# esp8266.net
KiCad netlist of a schematic drawn in EasyEDA Pro
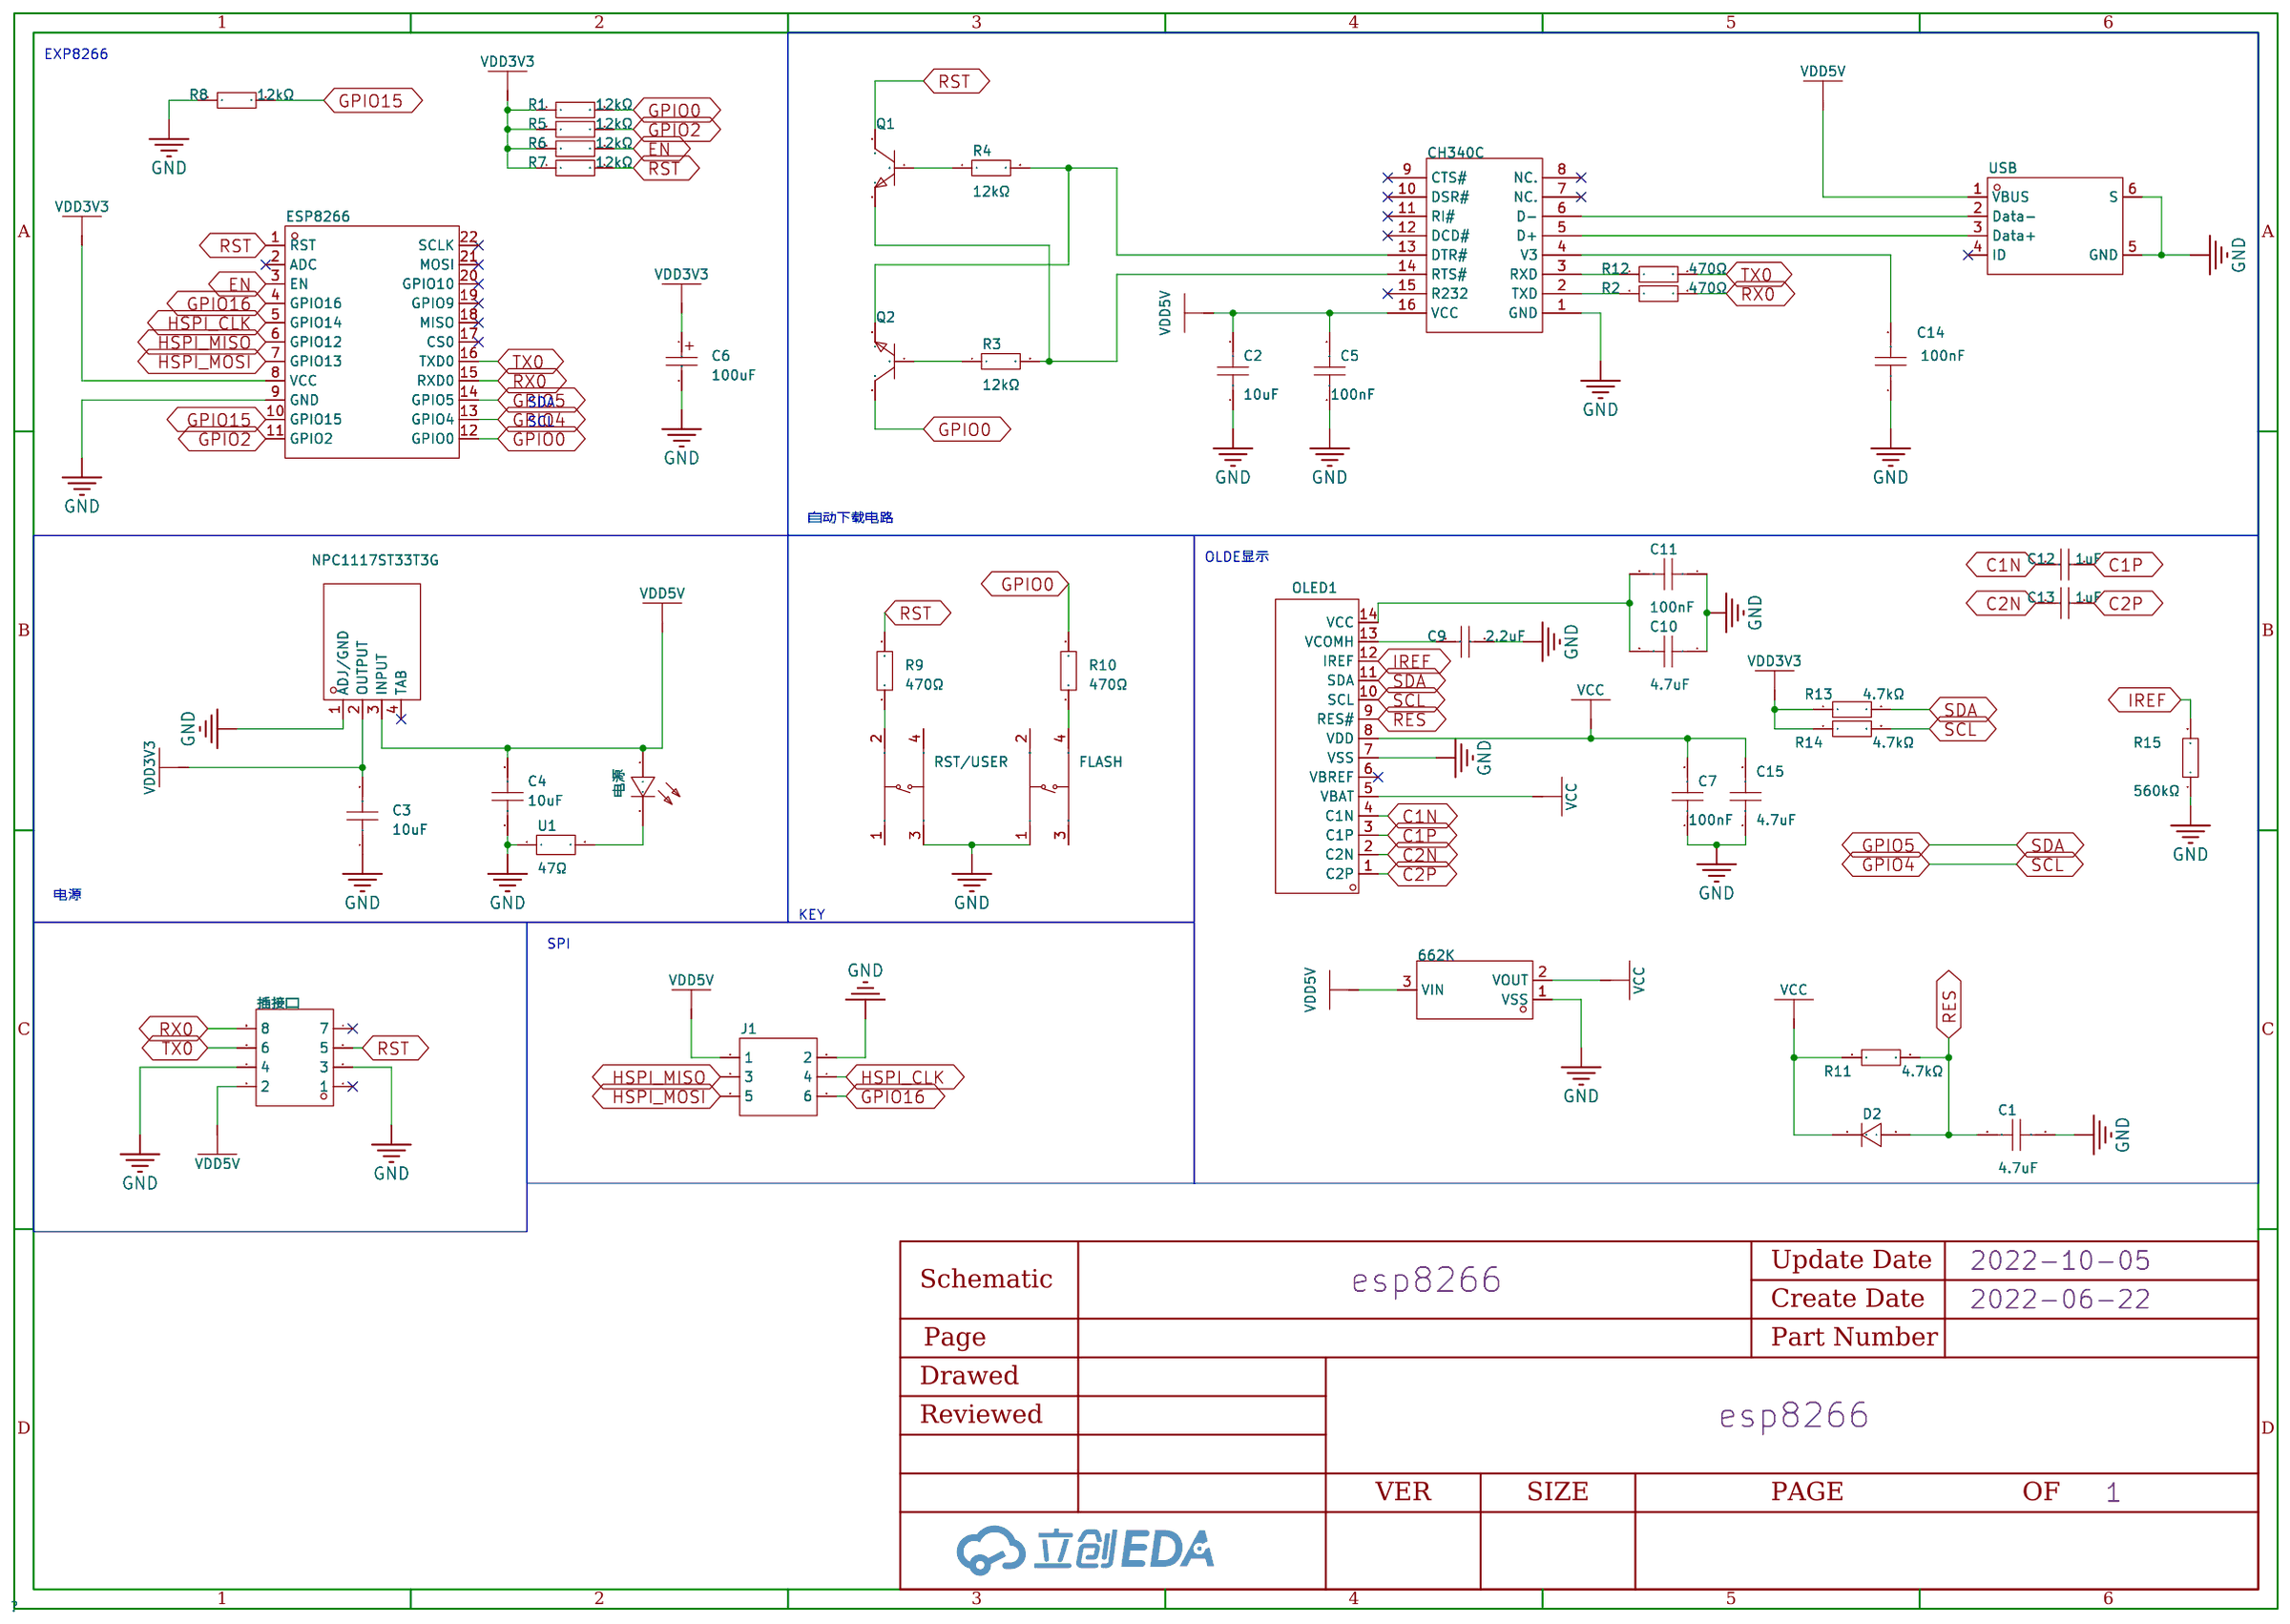
[diagram p0: schematic sheet]

(export (version "E")
  (design (tool "Eeschema 10.0.6"))
  (components
    (comp (ref "662K")
      (value "~")
      (footprint "easyedapro:SOT-23-3_L2.9-W1.3-P1.90-LS2.4-BR")
      (description "输出类型:-;")
      (fields (field (name "Manufacturer Part") "662K.") (field (name "Manufacturer") "FM富满"))
      (libsource (lib "easyedapro") (part "662K."))
    )
    (comp (ref "C1")
      (value "4.7uF")
      (footprint "easyedapro:C0805")
      (description "容值:4.7uF;精度:±10%;额定电压:25V;温度系数:X5R;")
      (fields
        (field (name "Manufacturer Part") "TMK212ABJ475KG-T")
        (field (name "Manufacturer") "TAIYO YUDEN(太诱)")
      )
      (libsource (lib "easyedapro") (part "TMK212ABJ475KG-T"))
    )
    (comp (ref "C2")
      (value "10uF")
      (footprint "easyedapro:C0805")
      (description "容值:10uF;精度:±10%;额定电压:-;温度系数:-;")
      (fields
        (field (name "Manufacturer Part") "GRT21BC71E106KE13L")
        (field (name "Manufacturer") "muRata(村田)")
      )
      (libsource (lib "easyedapro") (part "GRT21BC71E106KE13L"))
    )
    (comp (ref "C3")
      (value "10uF")
      (footprint "easyedapro:C0805")
      (description "容值:10uF;精度:±10%;额定电压:-;温度系数:-;")
      (fields
        (field (name "Manufacturer Part") "GRT21BC71E106KE13L")
        (field (name "Manufacturer") "muRata(村田)")
      )
      (libsource (lib "easyedapro") (part "GRT21BC71E106KE13L"))
    )
    (comp (ref "C4")
      (value "10uF")
      (footprint "easyedapro:C0805")
      (description "容值:10uF;精度:±10%;额定电压:-;温度系数:-;")
      (fields
        (field (name "Manufacturer Part") "GRT21BC71E106KE13L")
        (field (name "Manufacturer") "muRata(村田)")
      )
      (libsource (lib "easyedapro") (part "GRT21BC71E106KE13L"))
    )
    (comp (ref "C5")
      (value "100nF")
      (footprint "easyedapro:C0805")
      (description "容值:100nF;精度:±10%;额定电压:100V;温度系数:X7R;")
      (fields (field (name "Manufacturer Part") "C0805X104K101T") (field (name "Manufacturer") "IHHEC(禾伸堂)"))
      (libsource (lib "easyedapro") (part "C0805X104K101T_C485772"))
    )
    (comp (ref "C6")
      (value "100uF")
      (footprint "easyedapro:CAP-SMD_L3.5-W2.8-R-RD")
      (description "容值:100uF;精度:±20%;额定电压:6.3V;等效串联电阻:1.7Ω@100kHz;工作温度:-55~+125;")
      (fields (field (name "Manufacturer Part") "TAJB107M006RNJ") (field (name "Manufacturer") "AVX"))
      (libsource (lib "easyedapro") (part "TAJB107M006RNJ"))
    )
    (comp (ref "C7")
      (value "100nF")
      (footprint "easyedapro:C0805")
      (description "容值:100nF;精度:±10%;额定电压:100V;温度系数:X7R;")
      (fields (field (name "Manufacturer Part") "C0805X104K101T") (field (name "Manufacturer") "IHHEC(禾伸堂)"))
      (libsource (lib "easyedapro") (part "C0805X104K101T_C485772"))
    )
    (comp (ref "C9")
      (value "2.2uF")
      (footprint "easyedapro:C0805")
      (description "容值:2.2uF;精度:-20%~+80%;额定电压:25V;温度系数:Y5V;")
      (fields
        (field (name "Manufacturer Part") "CL21F225ZAFNNNE")
        (field (name "Manufacturer") "SAMSUNG(三星)")
      )
      (libsource (lib "easyedapro") (part "CL21F225ZAFNNNE"))
    )
    (comp (ref "C10")
      (value "4.7uF")
      (footprint "easyedapro:C0805")
      (description "容值:4.7uF;精度:±10%;额定电压:-;温度系数:-;")
      (fields
        (field (name "Manufacturer Part") "GRM219B31A475KE33D")
        (field (name "Manufacturer") "muRata(村田)")
      )
      (libsource (lib "easyedapro") (part "GRM219B31A475KE33D"))
    )
    (comp (ref "C11")
      (value "100nF")
      (footprint "easyedapro:C0805")
      (description "容值:100nF;精度:±10%;额定电压:100V;温度系数:X7R;")
      (fields (field (name "Manufacturer Part") "C0805X104K101T") (field (name "Manufacturer") "IHHEC(禾伸堂)"))
      (libsource (lib "easyedapro") (part "C0805X104K101T_C485772"))
    )
    (comp (ref "C12")
      (value "1uF")
      (footprint "easyedapro:C0805")
      (description "容值:1uF;精度:-20%~+80%;额定电压:16V;温度系数:Y5V;")
      (fields
        (field (name "Manufacturer Part") "CL21F105ZOFNNNE")
        (field (name "Manufacturer") "SAMSUNG(三星)")
      )
      (libsource (lib "easyedapro") (part "CL21F105ZOFNNNE"))
    )
    (comp (ref "C13")
      (value "1uF")
      (footprint "easyedapro:C0805")
      (description "容值:1uF;精度:-20%~+80%;额定电压:16V;温度系数:Y5V;")
      (fields
        (field (name "Manufacturer Part") "CL21F105ZOFNNNE")
        (field (name "Manufacturer") "SAMSUNG(三星)")
      )
      (libsource (lib "easyedapro") (part "CL21F105ZOFNNNE"))
    )
    (comp (ref "C14")
      (value "100nF")
      (footprint "easyedapro:C0805")
      (description "容值:100nF;精度:±10%;额定电压:100V;温度系数:X7R;")
      (fields (field (name "Manufacturer Part") "C0805X104K101T") (field (name "Manufacturer") "IHHEC(禾伸堂)"))
      (libsource (lib "easyedapro") (part "C0805X104K101T_C485772"))
    )
    (comp (ref "C15")
      (value "4.7uF")
      (footprint "easyedapro:C0805")
      (description "容值:4.7uF;精度:±10%;额定电压:25V;温度系数:X5R;")
      (fields
        (field (name "Manufacturer Part") "TMK212ABJ475KG-T")
        (field (name "Manufacturer") "TAIYO YUDEN(太诱)")
      )
      (libsource (lib "easyedapro") (part "TMK212ABJ475KG-T"))
    )
    (comp (ref "CH340C")
      (value "~")
      (footprint "easyedapro:SOP-16_L10.0-W3.9-P1.27-LS6.0-BL")
      (description "类型:Transceiver;协议类别:USB 2.0;驱动器/接收器数:-;数据速率:2Mbps;")
      (fields (field (name "Manufacturer Part") "CH340C") (field (name "Manufacturer") "WCH(南京沁恒)"))
      (libsource (lib "easyedapro") (part "CH340C"))
    )
    (comp (ref "D2")
      (value "~")
      (footprint "easyedapro:SOD-323_L1.8-W1.3-LS2.5-RD")
      (fields (field (name "Manufacturer Part") "1N4148WS") (field (name "Manufacturer") "CJ（江苏长电/长晶）"))
      (libsource (lib "easyedapro") (part "1N4148WS T4"))
    )
    (comp (ref "ESP8266")
      (value "~")
      (footprint "easyedapro:WIFIM-SMD_ESP-12F-ESP8266MOD")
      (description "屏蔽罩上的丝印是：ESP8266MOD，ESP8266EX串口WIFI")
      (fields
        (field (name "Manufacturer Part") "ESP-12F(ESP8266MOD)")
        (field (name "Manufacturer") "Ai-Thinker(安信可)")
      )
      (libsource (lib "easyedapro") (part "ESP-12F(ESP8266MOD)"))
    )
    (comp (ref "FLASH")
      (value "~")
      (footprint "easyedapro:SW-TH_4P-L6.0-W6.0-P4.50-LS6.5")
      (description "触点电流:50mA;额定电压(DC):12V;电路结构:单刀单掷;安装方式:直插;按钮形状:圆形按钮;带灯:-;开关长度:6mm;开关宽度:6mm;开关高度:5mm;")
      (fields (field (name "Manufacturer Part") "TS665CJ") (field (name "Manufacturer") "SHOU HAN(首韩)"))
      (libsource (lib "easyedapro") (part "TS665CJ"))
    )
    (comp (ref "J1")
      (value "~")
      (footprint "easyedapro:HDR-TH_6P-P2.54-V-M-R2-C3-S2.54-1")
      (fields (field (name "Manufacturer Part") "2.54-2*3P针") (field (name "Manufacturer") "BOOMELE(博穆精密)"))
      (libsource (lib "easyedapro") (part "Header-Male-2.54_2x3"))
    )
    (comp (ref "NPC1117ST33T3G")
      (value "~")
      (footprint "easyedapro:SOT-223-3_L6.5-W3.4-P2.30-LS7.0-BR")
      (description "输出类型:固定;输出极性:正;输出通道数:1;最大输入电压:20V;输出电压:3.3V;压差:1.2V@(800mA);输出电流:1A;电源纹波抑制比(PRSS):64dB@(120Hz);")
      (fields (field (name "Manufacturer Part") "NCP1117ST33T3G") (field (name "Manufacturer") "onsemi(安森美)"))
      (libsource (lib "easyedapro") (part "NCP1117ST33T3G"))
    )
    (comp (ref "OLED1")
      (value "~")
      (footprint "easyedapro:OLED_QG-2832TLBFG02")
      (fields
        (field (name "Manufacturer Part") "QG-2832TLBFG02")
        (field (name "Manufacturer") "全智景Allvision")
      )
      (libsource (lib "easyedapro") (part "QG-2832TLBFG02"))
    )
    (comp (ref "Q1")
      (value "~")
      (footprint "easyedapro:SOT-23-3_L2.9-W1.3-P1.90-LS2.4-BR")
      (fields (field (name "Manufacturer Part") "MMBT3904") (field (name "Manufacturer") "CJ（江苏长电/长晶）"))
      (libsource (lib "easyedapro") (part "MMBT3904"))
    )
    (comp (ref "Q2")
      (value "~")
      (footprint "easyedapro:SOT-23-3_L2.9-W1.3-P1.90-LS2.4-BR")
      (fields (field (name "Manufacturer Part") "MMBT3904") (field (name "Manufacturer") "CJ（江苏长电/长晶）"))
      (libsource (lib "easyedapro") (part "MMBT3904"))
    )
    (comp (ref "R1")
      (value "12kΩ")
      (footprint "easyedapro:R0805")
      (description "电阻类型:厚膜电阻;阻值:12kΩ;精度:±1%;功率:125mW;温度系数:±100ppm/;最大工作电压:150V;工作温度范围:-55~+155;")
      (fields
        (field (name "Manufacturer Part") "0805W8F1202T5E")
        (field (name "Manufacturer") "UNI-ROYAL(厚声)")
      )
      (libsource (lib "easyedapro") (part "0805W8F1202T5E"))
    )
    (comp (ref "R2")
      (value "470Ω")
      (footprint "easyedapro:R0805")
      (description "阻值:470Ω;精度:±1%;功率:125mW;温度系数:±100ppm/;最大工作电压:100V;工作温度范围:-55~+155;")
      (fields (field (name "Manufacturer Part") "RS-05K4700FT") (field (name "Manufacturer") "FH(风华)"))
      (libsource (lib "easyedapro") (part "RS-05K4700FT"))
    )
    (comp (ref "R3")
      (value "12kΩ")
      (footprint "easyedapro:R0805")
      (description "电阻类型:厚膜电阻;阻值:12kΩ;精度:±1%;功率:125mW;温度系数:±100ppm/;最大工作电压:150V;工作温度范围:-55~+155;")
      (fields
        (field (name "Manufacturer Part") "0805W8F1202T5E")
        (field (name "Manufacturer") "UNI-ROYAL(厚声)")
      )
      (libsource (lib "easyedapro") (part "0805W8F1202T5E"))
    )
    (comp (ref "R4")
      (value "12kΩ")
      (footprint "easyedapro:R0805")
      (description "电阻类型:厚膜电阻;阻值:12kΩ;精度:±1%;功率:125mW;温度系数:±100ppm/;最大工作电压:150V;工作温度范围:-55~+155;")
      (fields
        (field (name "Manufacturer Part") "0805W8F1202T5E")
        (field (name "Manufacturer") "UNI-ROYAL(厚声)")
      )
      (libsource (lib "easyedapro") (part "0805W8F1202T5E"))
    )
    (comp (ref "R5")
      (value "12kΩ")
      (footprint "easyedapro:R0805")
      (description "电阻类型:厚膜电阻;阻值:12kΩ;精度:±1%;功率:125mW;温度系数:±100ppm/;最大工作电压:150V;工作温度范围:-55~+155;")
      (fields
        (field (name "Manufacturer Part") "0805W8F1202T5E")
        (field (name "Manufacturer") "UNI-ROYAL(厚声)")
      )
      (libsource (lib "easyedapro") (part "0805W8F1202T5E"))
    )
    (comp (ref "R6")
      (value "12kΩ")
      (footprint "easyedapro:R0805")
      (description "电阻类型:厚膜电阻;阻值:12kΩ;精度:±1%;功率:125mW;温度系数:±100ppm/;最大工作电压:150V;工作温度范围:-55~+155;")
      (fields
        (field (name "Manufacturer Part") "0805W8F1202T5E")
        (field (name "Manufacturer") "UNI-ROYAL(厚声)")
      )
      (libsource (lib "easyedapro") (part "0805W8F1202T5E"))
    )
    (comp (ref "R7")
      (value "12kΩ")
      (footprint "easyedapro:R0805")
      (description "电阻类型:厚膜电阻;阻值:12kΩ;精度:±1%;功率:125mW;温度系数:±100ppm/;最大工作电压:150V;工作温度范围:-55~+155;")
      (fields
        (field (name "Manufacturer Part") "0805W8F1202T5E")
        (field (name "Manufacturer") "UNI-ROYAL(厚声)")
      )
      (libsource (lib "easyedapro") (part "0805W8F1202T5E"))
    )
    (comp (ref "R8")
      (value "12kΩ")
      (footprint "easyedapro:R0805")
      (description "电阻类型:厚膜电阻;阻值:12kΩ;精度:±1%;功率:125mW;温度系数:±100ppm/;最大工作电压:150V;工作温度范围:-55~+155;")
      (fields
        (field (name "Manufacturer Part") "0805W8F1202T5E")
        (field (name "Manufacturer") "UNI-ROYAL(厚声)")
      )
      (libsource (lib "easyedapro") (part "0805W8F1202T5E"))
    )
    (comp (ref "R9")
      (value "470Ω")
      (footprint "easyedapro:R0805")
      (description "阻值:470Ω;精度:±1%;功率:125mW;温度系数:±100ppm/;最大工作电压:100V;工作温度范围:-55~+155;")
      (fields (field (name "Manufacturer Part") "RS-05K4700FT") (field (name "Manufacturer") "FH(风华)"))
      (libsource (lib "easyedapro") (part "RS-05K4700FT"))
    )
    (comp (ref "R10")
      (value "470Ω")
      (footprint "easyedapro:R0805")
      (description "阻值:470Ω;精度:±1%;功率:125mW;温度系数:±100ppm/;最大工作电压:100V;工作温度范围:-55~+155;")
      (fields (field (name "Manufacturer Part") "RS-05K4700FT") (field (name "Manufacturer") "FH(风华)"))
      (libsource (lib "easyedapro") (part "RS-05K4700FT"))
    )
    (comp (ref "R11")
      (value "4.7kΩ")
      (footprint "easyedapro:R0805")
      (description "阻值:4.7kΩ;精度:±1%;功率:0.125W;")
      (fields (field (name "Manufacturer Part") "RMC08054.7K1%N") (field (name "Manufacturer") "Tyohm(幸亚电阻)"))
      (libsource (lib "easyedapro") (part "RMC08054.7K1%N"))
    )
    (comp (ref "R12")
      (value "470Ω")
      (footprint "easyedapro:R0805")
      (description "阻值:470Ω;精度:±1%;功率:125mW;温度系数:±100ppm/;最大工作电压:100V;工作温度范围:-55~+155;")
      (fields (field (name "Manufacturer Part") "RS-05K4700FT") (field (name "Manufacturer") "FH(风华)"))
      (libsource (lib "easyedapro") (part "RS-05K4700FT"))
    )
    (comp (ref "R13")
      (value "4.7kΩ")
      (footprint "easyedapro:R0805")
      (description "阻值:4.7kΩ;精度:±1%;功率:0.125W;")
      (fields (field (name "Manufacturer Part") "RMC08054.7K1%N") (field (name "Manufacturer") "Tyohm(幸亚电阻)"))
      (libsource (lib "easyedapro") (part "RMC08054.7K1%N"))
    )
    (comp (ref "R14")
      (value "4.7kΩ")
      (footprint "easyedapro:R0805")
      (description "阻值:4.7kΩ;精度:±1%;功率:0.125W;")
      (fields (field (name "Manufacturer Part") "RMC08054.7K1%N") (field (name "Manufacturer") "Tyohm(幸亚电阻)"))
      (libsource (lib "easyedapro") (part "RMC08054.7K1%N"))
    )
    (comp (ref "R15")
      (value "560kΩ")
      (footprint "easyedapro:R0805")
      (description "电阻类型:厚膜电阻;阻值:560kΩ;精度:±1%;功率:1/8W;温度系数:±100ppm/;最大工作电压:150V;工作温度范围:-55~+155;")
      (fields
        (field (name "Manufacturer Part") "0805W8F5603T5E")
        (field (name "Manufacturer") "UNI-ROYAL(厚声)")
      )
      (libsource (lib "easyedapro") (part "0805W8F5603T5E"))
    )
    (comp (ref "RST/USER")
      (value "~")
      (footprint "easyedapro:SW-TH_4P-L6.0-W6.0-P4.50-LS6.5")
      (description "触点电流:50mA;额定电压(DC):12V;电路结构:单刀单掷;安装方式:直插;按钮形状:圆形按钮;带灯:-;开关长度:6mm;开关宽度:6mm;开关高度:5mm;")
      (fields (field (name "Manufacturer Part") "TS665CJ") (field (name "Manufacturer") "SHOU HAN(首韩)"))
      (libsource (lib "easyedapro") (part "TS665CJ"))
    )
    (comp (ref "U1")
      (value "47Ω")
      (footprint "easyedapro:RES-TH_BD2.3-L3.7-P7.70-D0.4")
      (description "电阻类型:金属膜电阻;阻值:47Ω;精度:±1%;功率:125mW;温度系数:±350ppm/;最大工作电压:200V;工作温度范围:-55~+155;")
      (fields (field (name "Manufacturer Part") "MF1/8W-47Ω±1%-OT52") (field (name "Manufacturer") "VO(翔胜)"))
      (libsource (lib "easyedapro") (part "MF1/8W-47Ω±1%-OT52"))
    )
    (comp (ref "USB")
      (value "~")
      (footprint "easyedapro:MICRO-USB-SMD_10118194-0001LF")
      (description "连接器类型:Micro-B;标准:USB 2.0;公母:母座;触点数量:5;端口数量:1;")
      (fields (field (name "Manufacturer Part") "10118194-0001LF") (field (name "Manufacturer") "Amphenol"))
      (libsource (lib "easyedapro") (part "10118194-0001LF"))
    )
    (comp (ref "插接口")
      (value "~")
      (footprint "easyedapro:HDR-TH_8P-P2.54-H-R2-C4-S2.54-W10.0_A2541WR")
      (fields (field (name "Manufacturer Part") "A2541WR-2x4P") (field (name "Manufacturer") "CJT(长江连接器)"))
      (libsource (lib "easyedapro") (part "A2541WR-2X4P"))
    )
    (comp (ref "电源")
      (value "~")
      (footprint "easyedapro:LED-TH_BD3.0-P2.54-FD")
      (fields
        (field (name "Manufacturer Part") "204-10SURD/S530-A3-L")
        (field (name "Manufacturer") "EVERLIGHT(台湾亿光)")
      )
      (libsource (lib "easyedapro") (part "204-10SURD/S530-A3-L"))
    )
  )
  (nets
    (net (code "1") (name "C1N") (class "Default")
      (node (ref "C12") (pin "2") (pinfunction "2_2") (pintype "input"))
      (node (ref "OLED1") (pin "4") (pinfunction "C1N_4") (pintype "input"))
    )
    (net (code "2") (name "C1P") (class "Default")
      (node (ref "C12") (pin "1") (pinfunction "1_1") (pintype "input"))
      (node (ref "OLED1") (pin "3") (pinfunction "C1P_3") (pintype "input"))
    )
    (net (code "3") (name "C2N") (class "Default")
      (node (ref "C13") (pin "1") (pinfunction "1_1") (pintype "input"))
      (node (ref "OLED1") (pin "2") (pinfunction "C2N_2") (pintype "input"))
    )
    (net (code "4") (name "C2P") (class "Default")
      (node (ref "C13") (pin "2") (pinfunction "2_2") (pintype "input"))
      (node (ref "OLED1") (pin "1") (pinfunction "C2P_1") (pintype "input"))
    )
    (net (code "5") (name "EN") (class "Default")
      (node (ref "ESP8266") (pin "3") (pinfunction "EN_3") (pintype "input"))
      (node (ref "R6") (pin "2") (pinfunction "2_2") (pintype "input"))
    )
    (net (code "6") (name "GND") (class "Default")
      (node (ref "662K") (pin "1") (pinfunction "VSS_1") (pintype "input"))
      (node (ref "C1") (pin "1") (pinfunction "1_1") (pintype "input"))
      (node (ref "C10") (pin "1") (pinfunction "1_1") (pintype "input"))
      (node (ref "C11") (pin "1") (pinfunction "1_1") (pintype "input"))
      (node (ref "C14") (pin "1") (pinfunction "1_1") (pintype "input"))
      (node (ref "C15") (pin "1") (pinfunction "1_1") (pintype "input"))
      (node (ref "C2") (pin "1") (pinfunction "1_1") (pintype "input"))
      (node (ref "C3") (pin "1") (pinfunction "1_1") (pintype "input"))
      (node (ref "C4") (pin "1") (pinfunction "1_1") (pintype "input"))
      (node (ref "C5") (pin "1") (pinfunction "1_1") (pintype "input"))
      (node (ref "C6") (pin "2") (pinfunction "2_2") (pintype "input"))
      (node (ref "C7") (pin "1") (pinfunction "1_1") (pintype "input"))
      (node (ref "C9") (pin "1") (pinfunction "1_1") (pintype "input"))
      (node (ref "CH340C") (pin "1") (pinfunction "GND_1") (pintype "input"))
      (node (ref "ESP8266") (pin "9") (pinfunction "GND_9") (pintype "input"))
      (node (ref "FLASH") (pin "1") (pinfunction "A_1") (pintype "input"))
      (node (ref "J1") (pin "2") (pinfunction "2_2") (pintype "input"))
      (node (ref "NPC1117ST33T3G") (pin "1") (pinfunction "ADJ/GND_1") (pintype "input"))
      (node (ref "OLED1") (pin "7") (pinfunction "VSS_7") (pintype "input"))
      (node (ref "R15") (pin "1") (pinfunction "1_1") (pintype "input"))
      (node (ref "R8") (pin "1") (pinfunction "1_1") (pintype "input"))
      (node (ref "RST/USER") (pin "3") (pinfunction "C_3") (pintype "input"))
      (node (ref "U1") (pin "1") (pinfunction "1_1") (pintype "input"))
      (node (ref "USB") (pin "5") (pinfunction "GND_5") (pintype "input"))
      (node (ref "USB") (pin "6") (pinfunction "S_6") (pintype "input"))
      (node (ref "插接口") (pin "3") (pinfunction "3_3") (pintype "input"))
      (node (ref "插接口") (pin "4") (pinfunction "4_4") (pintype "input"))
    )
    (net (code "7") (name "GPIO0") (class "Default")
      (node (ref "ESP8266") (pin "12") (pinfunction "GPIO0_12") (pintype "input"))
      (node (ref "Q2") (pin "3") (pinfunction "C_3") (pintype "input"))
      (node (ref "R1") (pin "2") (pinfunction "2_2") (pintype "input"))
      (node (ref "R10") (pin "2") (pinfunction "2_2") (pintype "input"))
    )
    (net (code "8") (name "GPIO2") (class "Default")
      (node (ref "ESP8266") (pin "11") (pinfunction "GPIO2_11") (pintype "input"))
      (node (ref "R5") (pin "2") (pinfunction "2_2") (pintype "input"))
    )
    (net (code "9") (name "GPIO4") (class "Default")
      (node (ref "ESP8266") (pin "13") (pinfunction "GPIO4_13") (pintype "input"))
      (node (ref "OLED1") (pin "10") (pinfunction "SCL_10") (pintype "input"))
      (node (ref "R14") (pin "2") (pinfunction "2_2") (pintype "input"))
    )
    (net (code "10") (name "GPIO5") (class "Default")
      (node (ref "ESP8266") (pin "14") (pinfunction "GPIO5_14") (pintype "input"))
      (node (ref "OLED1") (pin "11") (pinfunction "SDA_11") (pintype "input"))
      (node (ref "R13") (pin "2") (pinfunction "2_2") (pintype "input"))
    )
    (net (code "11") (name "GPIO15") (class "Default")
      (node (ref "ESP8266") (pin "10") (pinfunction "GPIO15_10") (pintype "input"))
      (node (ref "R8") (pin "2") (pinfunction "2_2") (pintype "input"))
    )
    (net (code "12") (name "GPIO16") (class "Default")
      (node (ref "ESP8266") (pin "4") (pinfunction "GPIO16_4") (pintype "input"))
      (node (ref "J1") (pin "6") (pinfunction "6_6") (pintype "input"))
    )
    (net (code "13") (name "HSPI_CLK") (class "Default")
      (node (ref "ESP8266") (pin "5") (pinfunction "GPIO14_5") (pintype "input"))
      (node (ref "J1") (pin "4") (pinfunction "4_4") (pintype "input"))
    )
    (net (code "14") (name "HSPI_MISO") (class "Default")
      (node (ref "ESP8266") (pin "6") (pinfunction "GPIO12_6") (pintype "input"))
      (node (ref "J1") (pin "3") (pinfunction "3_3") (pintype "input"))
    )
    (net (code "15") (name "HSPI_MOSI") (class "Default")
      (node (ref "ESP8266") (pin "7") (pinfunction "GPIO13_7") (pintype "input"))
      (node (ref "J1") (pin "5") (pinfunction "5_5") (pintype "input"))
    )
    (net (code "16") (name "IREF") (class "Default")
      (node (ref "OLED1") (pin "12") (pinfunction "IREF_12") (pintype "input"))
      (node (ref "R15") (pin "2") (pinfunction "2_2") (pintype "input"))
    )
    (net (code "17") (name "Net-(CH340C-D+)") (class "Default")
      (node (ref "CH340C") (pin "5") (pinfunction "D+_5") (pintype "input"))
      (node (ref "USB") (pin "3") (pinfunction "Data+_3") (pintype "input"))
    )
    (net (code "18") (name "Net-(CH340C-D-)") (class "Default")
      (node (ref "CH340C") (pin "6") (pinfunction "D-_6") (pintype "input"))
      (node (ref "USB") (pin "2") (pinfunction "Data-_2") (pintype "input"))
    )
    (net (code "19") (name "Net-(CH340C-DTR#)") (class "Default")
      (node (ref "CH340C") (pin "13") (pinfunction "DTR#_13") (pintype "input"))
      (node (ref "Q2") (pin "2") (pinfunction "E_2") (pintype "input"))
      (node (ref "R4") (pin "2") (pinfunction "2_2") (pintype "input"))
    )
    (net (code "20") (name "Net-(CH340C-RTS#)") (class "Default")
      (node (ref "CH340C") (pin "14") (pinfunction "RTS#_14") (pintype "input"))
      (node (ref "Q1") (pin "2") (pinfunction "E_2") (pintype "input"))
      (node (ref "R3") (pin "2") (pinfunction "2_2") (pintype "input"))
    )
    (net (code "21") (name "Net-(CH340C-RXD)") (class "Default")
      (node (ref "CH340C") (pin "3") (pinfunction "RXD_3") (pintype "input"))
      (node (ref "R12") (pin "1") (pinfunction "1_1") (pintype "input"))
    )
    (net (code "22") (name "Net-(CH340C-TXD)") (class "Default")
      (node (ref "CH340C") (pin "2") (pinfunction "TXD_2") (pintype "input"))
      (node (ref "R2") (pin "1") (pinfunction "1_1") (pintype "input"))
    )
    (net (code "23") (name "Net-(CH340C-V3)") (class "Default")
      (node (ref "C14") (pin "2") (pinfunction "2_2") (pintype "input"))
      (node (ref "CH340C") (pin "4") (pinfunction "V3_4") (pintype "input"))
    )
    (net (code "24") (name "Net-(FLASH-D)") (class "Default")
      (node (ref "FLASH") (pin "4") (pinfunction "D_4") (pintype "input"))
      (node (ref "R10") (pin "1") (pinfunction "1_1") (pintype "input"))
    )
    (net (code "25") (name "Net-(OLED1-VCC)") (class "Default")
      (node (ref "C10") (pin "2") (pinfunction "2_2") (pintype "input"))
      (node (ref "C11") (pin "2") (pinfunction "2_2") (pintype "input"))
      (node (ref "OLED1") (pin "14") (pinfunction "VCC_14") (pintype "input"))
    )
    (net (code "26") (name "Net-(OLED1-VCOMH)") (class "Default")
      (node (ref "C9") (pin "2") (pinfunction "2_2") (pintype "input"))
      (node (ref "OLED1") (pin "13") (pinfunction "VCOMH_13") (pintype "input"))
    )
    (net (code "27") (name "Net-(Q1-B)") (class "Default")
      (node (ref "Q1") (pin "1") (pinfunction "B_1") (pintype "input"))
      (node (ref "R4") (pin "1") (pinfunction "1_1") (pintype "input"))
    )
    (net (code "28") (name "Net-(Q2-B)") (class "Default")
      (node (ref "Q2") (pin "1") (pinfunction "B_1") (pintype "input"))
      (node (ref "R3") (pin "1") (pinfunction "1_1") (pintype "input"))
    )
    (net (code "29") (name "Net-(RST/USER-B)") (class "Default")
      (node (ref "R9") (pin "1") (pinfunction "1_1") (pintype "input"))
      (node (ref "RST/USER") (pin "2") (pinfunction "B_2") (pintype "input"))
    )
    (net (code "30") (name "Net-(电源-K)") (class "Default")
      (node (ref "U1") (pin "2") (pinfunction "2_2") (pintype "input"))
      (node (ref "电源") (pin "2") (pinfunction "K_2") (pintype "input"))
    )
    (net (code "31") (name "RES") (class "Default")
      (node (ref "C1") (pin "2") (pinfunction "2_2") (pintype "input"))
      (node (ref "D2") (pin "2") (pinfunction "A_2") (pintype "input"))
      (node (ref "OLED1") (pin "9") (pinfunction "RES#_9") (pintype "input"))
      (node (ref "R11") (pin "2") (pinfunction "2_2") (pintype "input"))
    )
    (net (code "32") (name "RST") (class "Default")
      (node (ref "ESP8266") (pin "1") (pinfunction "RST_1") (pintype "input"))
      (node (ref "Q1") (pin "3") (pinfunction "C_3") (pintype "input"))
      (node (ref "R7") (pin "2") (pinfunction "2_2") (pintype "input"))
      (node (ref "R9") (pin "2") (pinfunction "2_2") (pintype "input"))
      (node (ref "插接口") (pin "5") (pinfunction "5_5") (pintype "input"))
    )
    (net (code "33") (name "RX0") (class "Default")
      (node (ref "ESP8266") (pin "15") (pinfunction "RXD0_15") (pintype "input"))
      (node (ref "R2") (pin "2") (pinfunction "2_2") (pintype "input"))
      (node (ref "插接口") (pin "8") (pinfunction "8_8") (pintype "input"))
    )
    (net (code "34") (name "TX0") (class "Default")
      (node (ref "ESP8266") (pin "16") (pinfunction "TXD0_16") (pintype "input"))
      (node (ref "R12") (pin "2") (pinfunction "2_2") (pintype "input"))
      (node (ref "插接口") (pin "6") (pinfunction "6_6") (pintype "input"))
    )
    (net (code "35") (name "VCC") (class "Default")
      (node (ref "662K") (pin "2") (pinfunction "VOUT_2") (pintype "input"))
      (node (ref "C15") (pin "2") (pinfunction "2_2") (pintype "input"))
      (node (ref "C7") (pin "2") (pinfunction "2_2") (pintype "input"))
      (node (ref "D2") (pin "1") (pinfunction "K_1") (pintype "input"))
      (node (ref "OLED1") (pin "5") (pinfunction "VBAT_5") (pintype "input"))
      (node (ref "OLED1") (pin "8") (pinfunction "VDD_8") (pintype "input"))
      (node (ref "R11") (pin "1") (pinfunction "1_1") (pintype "input"))
    )
    (net (code "36") (name "VDD3V3") (class "Default")
      (node (ref "C3") (pin "2") (pinfunction "2_2") (pintype "input"))
      (node (ref "C6") (pin "1") (pinfunction "1_1") (pintype "input"))
      (node (ref "ESP8266") (pin "8") (pinfunction "VCC_8") (pintype "input"))
      (node (ref "NPC1117ST33T3G") (pin "2") (pinfunction "OUTPUT_2") (pintype "input"))
      (node (ref "R1") (pin "1") (pinfunction "1_1") (pintype "input"))
      (node (ref "R13") (pin "1") (pinfunction "1_1") (pintype "input"))
      (node (ref "R14") (pin "1") (pinfunction "1_1") (pintype "input"))
      (node (ref "R5") (pin "1") (pinfunction "1_1") (pintype "input"))
      (node (ref "R6") (pin "1") (pinfunction "1_1") (pintype "input"))
      (node (ref "R7") (pin "1") (pinfunction "1_1") (pintype "input"))
    )
    (net (code "37") (name "VDD5V") (class "Default")
      (node (ref "662K") (pin "3") (pinfunction "VIN_3") (pintype "input"))
      (node (ref "C2") (pin "2") (pinfunction "2_2") (pintype "input"))
      (node (ref "C4") (pin "2") (pinfunction "2_2") (pintype "input"))
      (node (ref "C5") (pin "2") (pinfunction "2_2") (pintype "input"))
      (node (ref "CH340C") (pin "16") (pinfunction "VCC_16") (pintype "input"))
      (node (ref "J1") (pin "1") (pinfunction "1_1") (pintype "input"))
      (node (ref "NPC1117ST33T3G") (pin "3") (pinfunction "INPUT_3") (pintype "input"))
      (node (ref "USB") (pin "1") (pinfunction "VBUS_1") (pintype "input"))
      (node (ref "插接口") (pin "2") (pinfunction "2_2") (pintype "input"))
      (node (ref "电源") (pin "1") (pinfunction "A_1") (pintype "input"))
    )
    (net (code "38") (name "unconnected-(CH340C-CTS#-Pad9)") (class "Default")
      (node (ref "CH340C") (pin "9") (pinfunction "CTS#_9") (pintype "input+no_connect"))
    )
    (net (code "39") (name "unconnected-(CH340C-DCD#-Pad12)") (class "Default")
      (node (ref "CH340C") (pin "12") (pinfunction "DCD#_12") (pintype "input+no_connect"))
    )
    (net (code "40") (name "unconnected-(CH340C-DSR#-Pad10)") (class "Default")
      (node (ref "CH340C") (pin "10") (pinfunction "DSR#_10") (pintype "input+no_connect"))
    )
    (net (code "41") (name "unconnected-(CH340C-NC.-Pad7)") (class "Default")
      (node (ref "CH340C") (pin "7") (pinfunction "NC._7") (pintype "input+no_connect"))
    )
    (net (code "42") (name "unconnected-(CH340C-NC.-Pad8)") (class "Default")
      (node (ref "CH340C") (pin "8") (pinfunction "NC._8") (pintype "input+no_connect"))
    )
    (net (code "43") (name "unconnected-(CH340C-R232-Pad15)") (class "Default")
      (node (ref "CH340C") (pin "15") (pinfunction "R232_15") (pintype "input+no_connect"))
    )
    (net (code "44") (name "unconnected-(CH340C-RI#-Pad11)") (class "Default")
      (node (ref "CH340C") (pin "11") (pinfunction "RI#_11") (pintype "input+no_connect"))
    )
    (net (code "45") (name "unconnected-(ESP8266-ADC-Pad2)") (class "Default")
      (node (ref "ESP8266") (pin "2") (pinfunction "ADC_2") (pintype "input+no_connect"))
    )
    (net (code "46") (name "unconnected-(ESP8266-CS0-Pad17)") (class "Default")
      (node (ref "ESP8266") (pin "17") (pinfunction "CS0_17") (pintype "input+no_connect"))
    )
    (net (code "47") (name "unconnected-(ESP8266-GPIO9-Pad19)") (class "Default")
      (node (ref "ESP8266") (pin "19") (pinfunction "GPIO9_19") (pintype "input+no_connect"))
    )
    (net (code "48") (name "unconnected-(ESP8266-GPIO10-Pad20)") (class "Default")
      (node (ref "ESP8266") (pin "20") (pinfunction "GPIO10_20") (pintype "input+no_connect"))
    )
    (net (code "49") (name "unconnected-(ESP8266-MISO-Pad18)") (class "Default")
      (node (ref "ESP8266") (pin "18") (pinfunction "MISO_18") (pintype "input+no_connect"))
    )
    (net (code "50") (name "unconnected-(ESP8266-MOSI-Pad21)") (class "Default")
      (node (ref "ESP8266") (pin "21") (pinfunction "MOSI_21") (pintype "input+no_connect"))
    )
    (net (code "51") (name "unconnected-(ESP8266-SCLK-Pad22)") (class "Default")
      (node (ref "ESP8266") (pin "22") (pinfunction "SCLK_22") (pintype "input+no_connect"))
    )
    (net (code "52") (name "unconnected-(FLASH-B-Pad2)") (class "Default")
      (node (ref "FLASH") (pin "2") (pinfunction "B_2") (pintype "input"))
    )
    (net (code "53") (name "unconnected-(FLASH-C-Pad3)") (class "Default")
      (node (ref "FLASH") (pin "3") (pinfunction "C_3") (pintype "input"))
    )
    (net (code "54") (name "unconnected-(NPC1117ST33T3G-TAB-Pad4)") (class "Default")
      (node (ref "NPC1117ST33T3G") (pin "4") (pinfunction "TAB_4") (pintype "input+no_connect"))
    )
    (net (code "55") (name "unconnected-(OLED1-VBREF-Pad6)") (class "Default")
      (node (ref "OLED1") (pin "6") (pinfunction "VBREF_6") (pintype "input+no_connect"))
    )
    (net (code "56") (name "unconnected-(RST/USER-A-Pad1)") (class "Default")
      (node (ref "RST/USER") (pin "1") (pinfunction "A_1") (pintype "input"))
    )
    (net (code "57") (name "unconnected-(RST/USER-D-Pad4)") (class "Default")
      (node (ref "RST/USER") (pin "4") (pinfunction "D_4") (pintype "input"))
    )
    (net (code "58") (name "unconnected-(USB-ID-Pad4)") (class "Default")
      (node (ref "USB") (pin "4") (pinfunction "ID_4") (pintype "input+no_connect"))
    )
    (net (code "59") (name "unconnected-(插接口-Pad1)") (class "Default")
      (node (ref "插接口") (pin "1") (pinfunction "1_1") (pintype "input+no_connect"))
    )
    (net (code "60") (name "unconnected-(插接口-Pad7)") (class "Default")
      (node (ref "插接口") (pin "7") (pinfunction "7_7") (pintype "input+no_connect"))
    )
  )
)
